# V4-AddRS485-1W-V01-016-defect.net
KiCad netlist of a schematic drawn in EAGLE
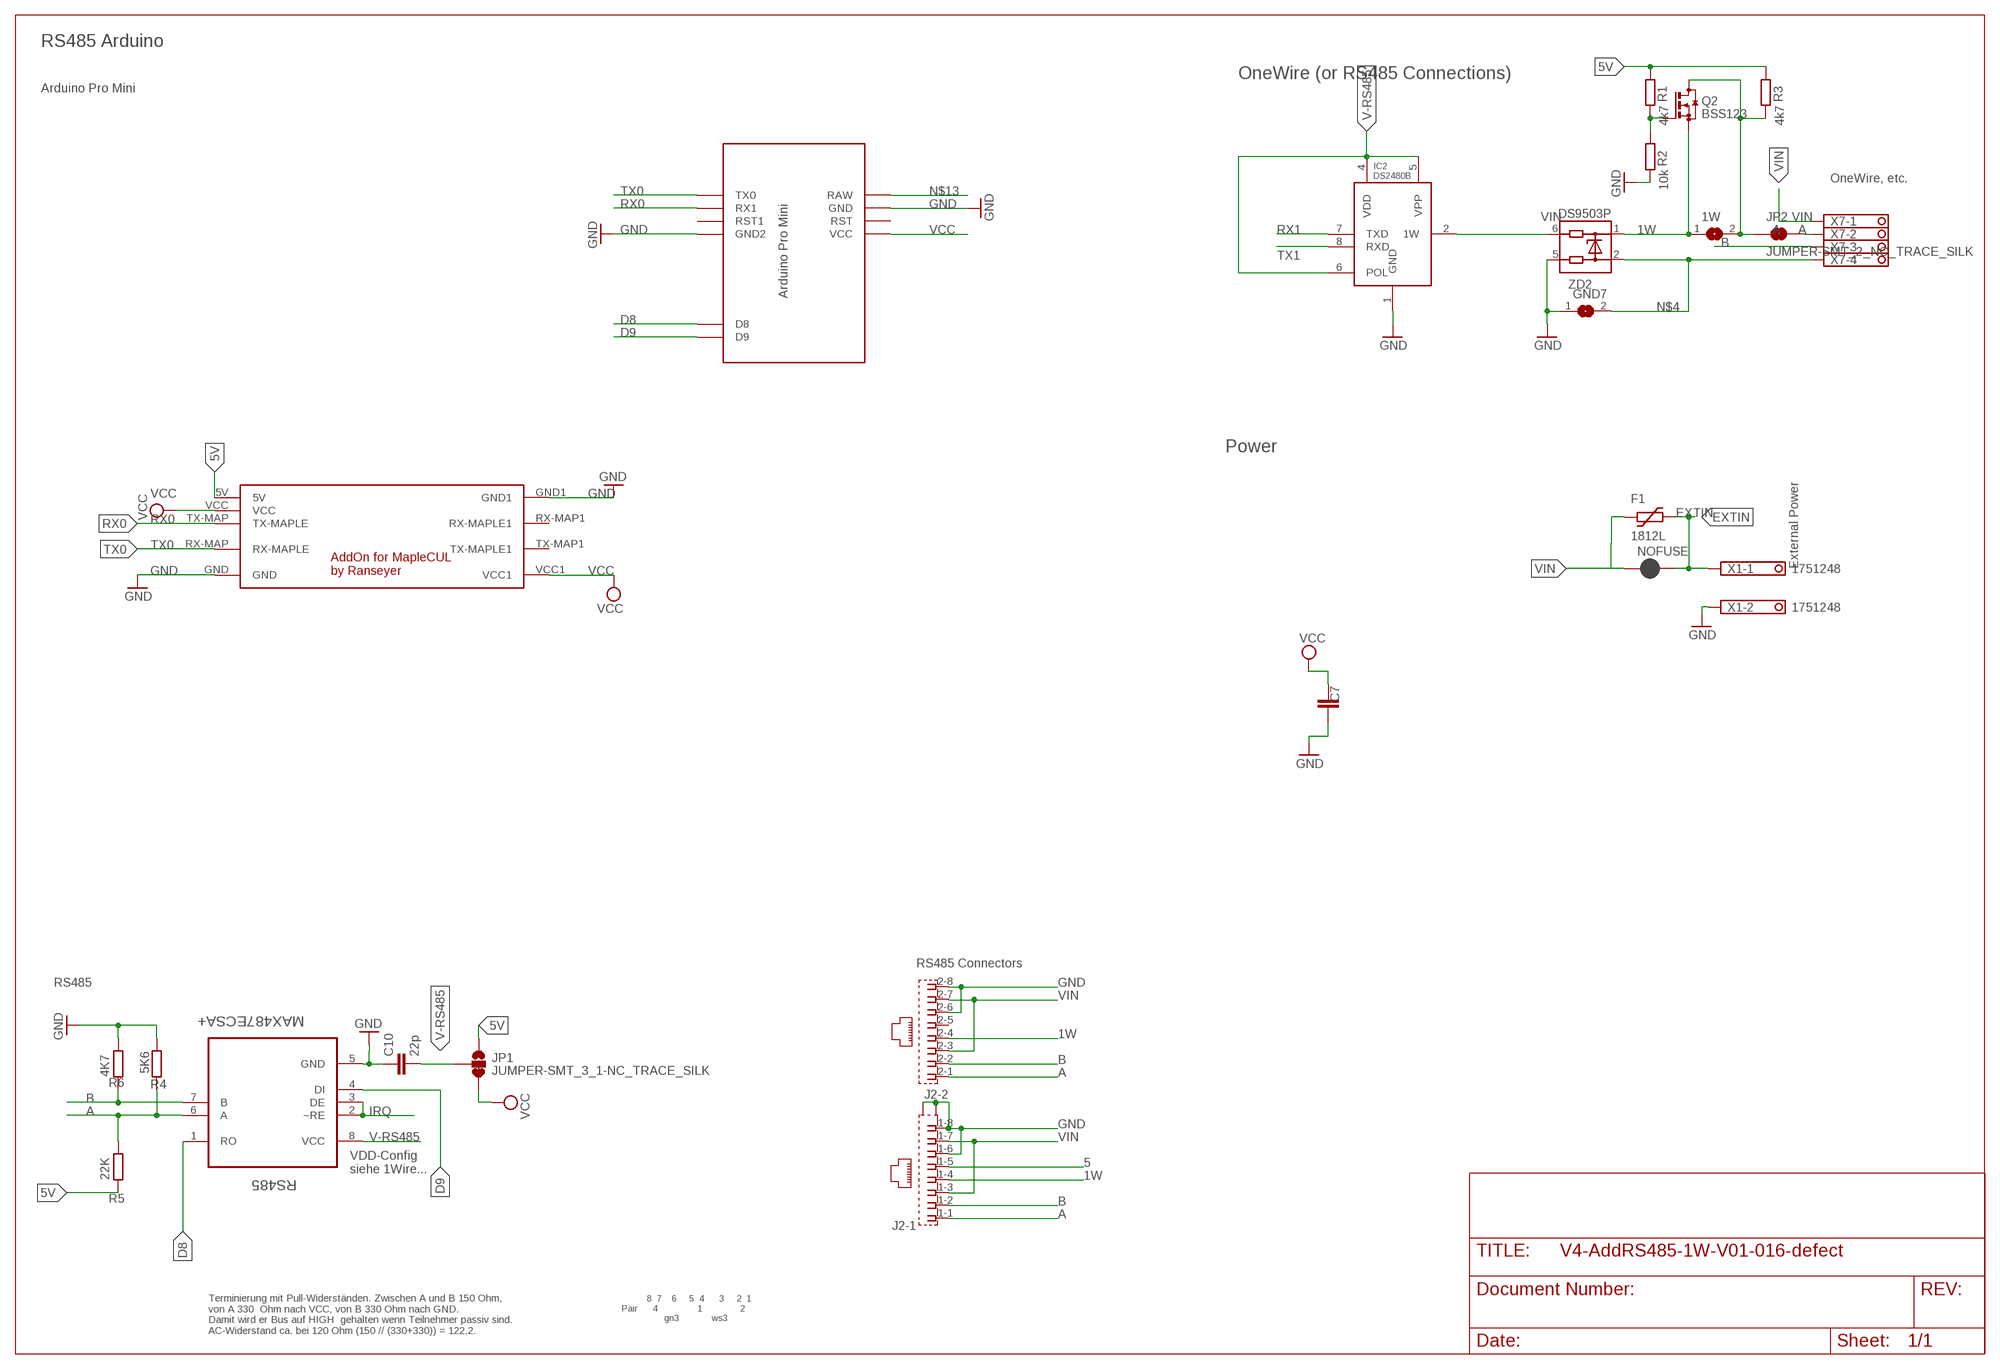
[diagram p0: schematic, sheet 1]

(export (version "E")
  (design (tool "Eeschema 10.0.6"))
  (components
    (comp (ref "1W") (value "SJ") (footprint "eagle-import:SJ") (libsource (lib "eagle-import") (part "SJ")))
    (comp (ref "C7")
      (value "C-EUC1812")
      (footprint "eagle-import:C1812")
      (libsource (lib "eagle-import") (part "rcl_334_C-EUC1812"))
    )
    (comp (ref "C10")
      (value "22p")
      (footprint "eagle-import:C0805")
      (libsource (lib "eagle-import") (part "C-EUC0805"))
    )
    (comp (ref "F1")
      (value "1812L")
      (footprint "eagle-import:1812L")
      (libsource (lib "eagle-import") (part "1812L"))
    )
    (comp (ref "GND7")
      (value "SJ")
      (footprint "eagle-import:SJ")
      (libsource (lib "eagle-import") (part "SJ"))
    )
    (comp (ref "IC2")
      (value "DS2480B")
      (footprint "eagle-import:SO08")
      (libsource (lib "eagle-import") (part "DS2480B"))
    )
    (comp (ref "J2")
      (value "RJ45_2X_S")
      (footprint "eagle-import:RJ45_2X_S")
      (libsource (lib "eagle-import") (part "RJ45_2X_S"))
    )
    (comp (ref "JP1")
      (value "JUMPER-SMT_3_1-NC_TRACE_SILK")
      (footprint "eagle-import:SMT-JUMPER_3_1-NC_TRACE_SILK")
      (libsource (lib "eagle-import") (part "JUMPER-SMT_3_1-NC_TRACE_SILK"))
    )
    (comp (ref "JP2")
      (value "JUMPER-SMT_2_NC_TRACE_SILK")
      (footprint "eagle-import:SMT-JUMPER_2_NC_TRACE_SILK")
      (libsource (lib "eagle-import") (part "JUMPER-SMT_2_NC_TRACE_SILK"))
    )
    (comp (ref "NOFUSE")
      (value "JUMPER-SMT_2_NC_PASTE_NO-SILK")
      (footprint "eagle-import:SMT-JUMPER_2_NC_PASTE_NO-SILK")
      (libsource (lib "eagle-import") (part "JUMPER-SMT_2_NC_PASTE_NO-SILK"))
    )
    (comp (ref "Q2")
      (value "BSS123")
      (footprint "eagle-import:SOT23")
      (libsource (lib "eagle-import") (part "BSS123"))
    )
    (comp (ref "R1")
      (value "4k7")
      (footprint "eagle-import:R0805")
      (libsource (lib "eagle-import") (part "R-EU_R0805"))
    )
    (comp (ref "R2")
      (value "10k")
      (footprint "eagle-import:R0805")
      (libsource (lib "eagle-import") (part "R-EU_R0805"))
    )
    (comp (ref "R3")
      (value "4k7")
      (footprint "eagle-import:R0805")
      (libsource (lib "eagle-import") (part "R-EU_R0805"))
    )
    (comp (ref "R4")
      (value "5K6")
      (footprint "eagle-import:R0805")
      (libsource (lib "eagle-import") (part "R-EU_R0805"))
    )
    (comp (ref "R5")
      (value "22K")
      (footprint "eagle-import:R0805")
      (libsource (lib "eagle-import") (part "R-EU_R0805"))
    )
    (comp (ref "R6")
      (value "4K7")
      (footprint "eagle-import:R0805")
      (libsource (lib "eagle-import") (part "R-EU_R0805"))
    )
    (comp (ref "RS485")
      (value "MAX487ECSA+")
      (footprint "eagle-import:SOIC127P600X175-8N")
      (libsource (lib "eagle-import") (part "MAX487ECSA+"))
    )
    (comp (ref "U$2")
      (value "MAPLE-CUL-ADDON-V01")
      (footprint "eagle-import:MAPLE-CUL-V01")
      (libsource (lib "eagle-import") (part "MAPLE-CUL-ADDON-V01"))
    )
    (comp (ref "U$3")
      (value "MARTIN-PRO-MINI-RS485")
      (footprint "eagle-import:MARTIN-PRO-MINI-RS485")
      (libsource (lib "eagle-import") (part "MARTIN-PRO-MINI-RS485"))
    )
    (comp (ref "X1")
      (value "1751248")
      (footprint "eagle-import:1751248")
      (libsource (lib "eagle-import") (part "1751248"))
    )
    (comp (ref "X7")
      (value "1751264")
      (footprint "eagle-import:1751264")
      (libsource (lib "eagle-import") (part "1751264"))
    )
    (comp (ref "ZD2")
      (value "DS9503P")
      (footprint "eagle-import:TSOC6")
      (libsource (lib "eagle-import") (part "DS9503P"))
    )
  )
  (nets
    (net (code "1") (name "/1W") (class "Default")
      (node (ref "1W") (pin "1") (pinfunction "1_1") (pintype "passive"))
      (node (ref "J2") (pin "1-4") (pinfunction "4_1-4") (pintype "passive"))
      (node (ref "J2") (pin "2-4") (pinfunction "4_2-4") (pintype "passive"))
      (node (ref "Q2") (pin "2") (pinfunction "S_2") (pintype "passive"))
      (node (ref "ZD2") (pin "1") (pinfunction "P$1_1") (pintype "passive"))
    )
    (net (code "2") (name "/5") (class "Default")
      (node (ref "J2") (pin "1-5") (pinfunction "5_1-5") (pintype "passive"))
    )
    (net (code "3") (name "/A") (class "Default")
      (node (ref "1W") (pin "2") (pinfunction "2_2") (pintype "passive"))
      (node (ref "J2") (pin "1-1") (pinfunction "1_1-1") (pintype "passive"))
      (node (ref "J2") (pin "2-1") (pinfunction "1_2-1") (pintype "passive"))
      (node (ref "JP2") (pin "1") (pinfunction "1_1") (pintype "passive"))
      (node (ref "JP2") (pin "2") (pinfunction "2_2") (pintype "passive"))
      (node (ref "Q2") (pin "3") (pinfunction "D_3") (pintype "passive"))
      (node (ref "R3") (pin "2") (pinfunction "2_2") (pintype "passive"))
      (node (ref "R4") (pin "2") (pinfunction "2_2") (pintype "passive"))
      (node (ref "R5") (pin "2") (pinfunction "2_2") (pintype "passive"))
      (node (ref "RS485") (pin "6") (pinfunction "A_6") (pintype "bidirectional"))
      (node (ref "X7") (pin "2") (pinfunction "K_2") (pintype "passive"))
    )
    (net (code "4") (name "/B") (class "Default")
      (node (ref "J2") (pin "1-2") (pinfunction "2_1-2") (pintype "passive"))
      (node (ref "J2") (pin "2-2") (pinfunction "2_2-2") (pintype "passive"))
      (node (ref "R6") (pin "1") (pinfunction "1_1") (pintype "passive"))
      (node (ref "RS485") (pin "7") (pinfunction "B_7") (pintype "bidirectional"))
      (node (ref "X7") (pin "3") (pinfunction "K_3") (pintype "passive"))
    )
    (net (code "5") (name "/IRQ") (class "Default")
      (node (ref "RS485") (pin "2") (pinfunction "~{RE}_2") (pintype "input"))
      (node (ref "RS485") (pin "3") (pinfunction "DE_3") (pintype "input"))
    )
    (net (code "6") (name "/N$4") (class "Default")
      (node (ref "GND7") (pin "2") (pinfunction "2_2") (pintype "passive"))
      (node (ref "X7") (pin "4") (pinfunction "K_4") (pintype "passive"))
      (node (ref "ZD2") (pin "2") (pinfunction "P$2_2") (pintype "passive"))
    )
    (net (code "7") (name "/N$13") (class "Default")
      (node (ref "U$3") (pin "RAW") (pinfunction "RAW_RAW") (pintype "bidirectional"))
    )
    (net (code "8") (name "/RX1") (class "Default")
      (node (ref "IC2") (pin "7") (pinfunction "TXD_7") (pintype "input"))
    )
    (net (code "9") (name "/TX1") (class "Default")
      (node (ref "IC2") (pin "8") (pinfunction "RXD_8") (pintype "output"))
    )
    (net (code "10") (name "5V") (class "Default")
      (node (ref "JP1") (pin "1") (pinfunction "1_1") (pintype "passive"))
      (node (ref "R1") (pin "1") (pinfunction "1_1") (pintype "passive"))
      (node (ref "R3") (pin "1") (pinfunction "1_1") (pintype "passive"))
      (node (ref "R5") (pin "1") (pinfunction "1_1") (pintype "passive"))
      (node (ref "U$2") (pin "5V") (pinfunction "5V_5V") (pintype "bidirectional"))
    )
    (net (code "11") (name "D8") (class "Default")
      (node (ref "RS485") (pin "1") (pinfunction "RO_1") (pintype "output"))
      (node (ref "U$3") (pin "D8") (pinfunction "D8_D8") (pintype "bidirectional"))
    )
    (net (code "12") (name "D9") (class "Default")
      (node (ref "RS485") (pin "4") (pinfunction "DI_4") (pintype "input"))
      (node (ref "U$3") (pin "D9") (pinfunction "D9_D9") (pintype "bidirectional"))
    )
    (net (code "13") (name "EXTIN") (class "Default")
      (node (ref "F1") (pin "P$2") (pinfunction "2_P$2") (pintype "passive"))
      (node (ref "NOFUSE") (pin "2") (pinfunction "2_2") (pintype "passive"))
      (node (ref "X1") (pin "1") (pinfunction "K_1") (pintype "passive"))
    )
    (net (code "14") (name "GND") (class "Default")
      (node (ref "C10") (pin "1") (pinfunction "1_1") (pintype "passive"))
      (node (ref "C7") (pin "1") (pinfunction "1_1") (pintype "passive"))
      (node (ref "GND7") (pin "1") (pinfunction "1_1") (pintype "passive"))
      (node (ref "IC2") (pin "1") (pinfunction "GND_1") (pintype "power_in"))
      (node (ref "J2") (pin "1-6") (pinfunction "6_1-6") (pintype "passive"))
      (node (ref "J2") (pin "1-8") (pinfunction "8_1-8") (pintype "passive"))
      (node (ref "J2") (pin "2-6") (pinfunction "6_2-6") (pintype "passive"))
      (node (ref "J2") (pin "2-8") (pinfunction "8_2-8") (pintype "passive"))
      (node (ref "J2") (pin "G1") (pinfunction "S2_G1") (pintype "passive"))
      (node (ref "J2") (pin "G3") (pinfunction "S1_G3") (pintype "passive"))
      (node (ref "R2") (pin "2") (pinfunction "2_2") (pintype "passive"))
      (node (ref "R4") (pin "1") (pinfunction "1_1") (pintype "passive"))
      (node (ref "R6") (pin "2") (pinfunction "2_2") (pintype "passive"))
      (node (ref "RS485") (pin "5") (pinfunction "GND_5") (pintype "passive"))
      (node (ref "U$2") (pin "GND") (pinfunction "GND_GND") (pintype "bidirectional"))
      (node (ref "U$2") (pin "GND1") (pinfunction "GND1_GND1") (pintype "bidirectional"))
      (node (ref "U$3") (pin "GND") (pinfunction "GND_GND") (pintype "bidirectional"))
      (node (ref "U$3") (pin "GND1") (pinfunction "GND2_GND1") (pintype "bidirectional"))
      (node (ref "X1") (pin "2") (pinfunction "K_2") (pintype "passive"))
      (node (ref "ZD2") (pin "5") (pinfunction "P$3_5") (pintype "passive"))
    )
    (net (code "15") (name "Net-(C10-Pad2)") (class "Default")
      (node (ref "C10") (pin "2") (pinfunction "2_2") (pintype "passive"))
      (node (ref "JP1") (pin "2") (pinfunction "2_2") (pintype "passive"))
    )
    (net (code "16") (name "Net-(IC2-1W)") (class "Default")
      (node (ref "IC2") (pin "2") (pinfunction "1W_2") (pintype "open_collector"))
      (node (ref "ZD2") (pin "6") (pinfunction "P$4_6") (pintype "passive"))
    )
    (net (code "17") (name "Net-(Q2-G)") (class "Default")
      (node (ref "Q2") (pin "1") (pinfunction "G_1") (pintype "passive"))
      (node (ref "R1") (pin "2") (pinfunction "2_2") (pintype "passive"))
      (node (ref "R2") (pin "1") (pinfunction "1_1") (pintype "passive"))
    )
    (net (code "18") (name "RX0") (class "Default")
      (node (ref "U$2") (pin "TX-MAP") (pinfunction "TX-MAPLE_TX-MAP") (pintype "bidirectional"))
      (node (ref "U$3") (pin "RX1") (pinfunction "RX1_RX1") (pintype "bidirectional"))
    )
    (net (code "19") (name "TX0") (class "Default")
      (node (ref "U$2") (pin "RX-MAP") (pinfunction "RX-MAPLE_RX-MAP") (pintype "bidirectional"))
      (node (ref "U$3") (pin "TX0") (pinfunction "TX0_TX0") (pintype "bidirectional"))
    )
    (net (code "20") (name "V-RS485") (class "Default")
      (node (ref "IC2") (pin "4") (pinfunction "VDD_4") (pintype "power_in"))
      (node (ref "IC2") (pin "5") (pinfunction "VPP_5") (pintype "power_in"))
      (node (ref "IC2") (pin "6") (pinfunction "POL_6") (pintype "input"))
      (node (ref "RS485") (pin "8") (pinfunction "VCC_8") (pintype "power_in"))
    )
    (net (code "21") (name "VCC") (class "Default")
      (node (ref "C7") (pin "2") (pinfunction "2_2") (pintype "passive"))
      (node (ref "JP1") (pin "3") (pinfunction "3_3") (pintype "passive"))
      (node (ref "U$2") (pin "VCC") (pinfunction "VCC_VCC") (pintype "bidirectional"))
      (node (ref "U$2") (pin "VCC1") (pinfunction "VCC1_VCC1") (pintype "bidirectional"))
      (node (ref "U$3") (pin "VCC") (pinfunction "VCC_VCC") (pintype "bidirectional"))
    )
    (net (code "22") (name "VIN") (class "Default")
      (node (ref "F1") (pin "P$1") (pinfunction "1_P$1") (pintype "passive"))
      (node (ref "J2") (pin "1-3") (pinfunction "3_1-3") (pintype "passive"))
      (node (ref "J2") (pin "1-7") (pinfunction "7_1-7") (pintype "passive"))
      (node (ref "J2") (pin "2-3") (pinfunction "3_2-3") (pintype "passive"))
      (node (ref "J2") (pin "2-7") (pinfunction "7_2-7") (pintype "passive"))
      (node (ref "NOFUSE") (pin "1") (pinfunction "1_1") (pintype "passive"))
      (node (ref "X7") (pin "1") (pinfunction "K_1") (pintype "passive"))
    )
    (net (code "23") (name "unconnected-(J2B-5-Pad2-5)") (class "Default")
      (node (ref "J2") (pin "2-5") (pinfunction "5_2-5") (pintype "passive"))
    )
    (net (code "24") (name "unconnected-(U$2-RX-MAPLE1-PadRX-MAP1)") (class "Default")
      (node (ref "U$2") (pin "RX-MAP1") (pinfunction "RX-MAPLE1_RX-MAP1") (pintype "bidirectional"))
    )
    (net (code "25") (name "unconnected-(U$2-TX-MAPLE1-PadTX-MAP1)") (class "Default")
      (node (ref "U$2") (pin "TX-MAP1") (pinfunction "TX-MAPLE1_TX-MAP1") (pintype "bidirectional"))
    )
    (net (code "26") (name "unconnected-(U$3-PadRST)") (class "Default")
      (node (ref "U$3") (pin "RST") (pinfunction "RST_RST") (pintype "bidirectional"))
    )
    (net (code "27") (name "unconnected-(U$3-PadRST1)") (class "Default")
      (node (ref "U$3") (pin "RST1") (pinfunction "RST1_RST1") (pintype "bidirectional"))
    )
  )
)
